# SH5_-_RGB_LED.net
KiCad netlist of a schematic drawn in Altium Designer
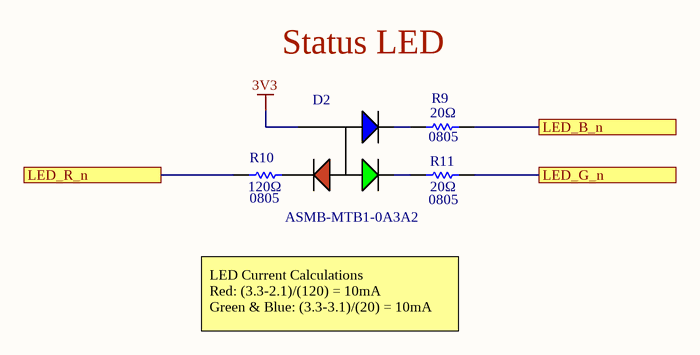
[diagram p0: SH5 - RGB LED.SchDoc]

(export (version "E")
  (design (tool "Eeschema 10.0.6"))
  (components
    (comp (ref "D2")
      (value "LED_RGB")
      (footprint "LED_RGB")
      (description "LED RGB DIFFUSED 4PLCC SMD")
      (fields (field (name "MANUFACTURER PART NUMBER 1") "ASMB-MTB1-0A3A2"))
      (libsource (lib "UWRT_Schematic_Library_2020") (part "LED_RGB"))
    )
    (comp (ref "R9")
      (value "20Ω")
      (footprint "RESC0805")
      (description "RES 20 OHM 1% 1/8W 0805")
      (fields
        (field (name "LCSC PART #") "C17581")
        (field (name "PACKAGE/FOOTPRINT") "0805")
        (field (name "Comment") "RES_20Ω_0805_1%")
      )
      (libsource (lib "UWRT_Schematic_Library_2020") (part "RES_20Ω_0805_1%"))
    )
    (comp (ref "R10")
      (value "120Ω")
      (footprint "RESC0805")
      (description "RES 120 OHM 1% 1/8W 0805")
      (fields
        (field (name "LCSC PART #") "C17437")
        (field (name "PACKAGE/FOOTPRINT") "0805")
        (field (name "Comment") "RES_120Ω_0805_1%")
      )
      (libsource (lib "UWRT_Schematic_Library_2020") (part "RES_120Ω_0805_1%"))
    )
    (comp (ref "R11")
      (value "20Ω")
      (footprint "RESC0805")
      (description "RES 20 OHM 1% 1/8W 0805")
      (fields
        (field (name "LCSC PART #") "C17581")
        (field (name "PACKAGE/FOOTPRINT") "0805")
        (field (name "Comment") "RES_20Ω_0805_1%")
      )
      (libsource (lib "UWRT_Schematic_Library_2020") (part "RES_20Ω_0805_1%"))
    )
  )
  (nets
    (net (code "1") (name "/LED_B_n") (class "Default")
      (node (ref "R9") (pin "2") (pinfunction "2_2") (pintype "passive"))
    )
    (net (code "2") (name "/LED_G_n") (class "Default")
      (node (ref "R11") (pin "2") (pinfunction "2_2") (pintype "passive"))
    )
    (net (code "3") (name "/LED_R_n") (class "Default")
      (node (ref "R10") (pin "1") (pinfunction "1_1") (pintype "passive"))
    )
    (net (code "4") (name "3V3") (class "Default")
      (node (ref "D2") (pin "4") (pinfunction "COMMON_ANODE_4") (pintype "passive"))
    )
    (net (code "5") (name "Net-(D2-CATHODE_(BLUE))") (class "Default")
      (node (ref "D2") (pin "3") (pinfunction "CATHODE_(BLUE)_3") (pintype "passive"))
      (node (ref "R9") (pin "1") (pinfunction "1_1") (pintype "passive"))
    )
    (net (code "6") (name "Net-(D2-CATHODE_(GREEN))") (class "Default")
      (node (ref "D2") (pin "2") (pinfunction "CATHODE_(GREEN)_2") (pintype "passive"))
      (node (ref "R11") (pin "1") (pinfunction "1_1") (pintype "passive"))
    )
    (net (code "7") (name "Net-(D2-CATHODE_(RED))") (class "Default")
      (node (ref "D2") (pin "1") (pinfunction "CATHODE_(RED)_1") (pintype "passive"))
      (node (ref "R10") (pin "2") (pinfunction "2_2") (pintype "passive"))
    )
  )
)
